# PQ60_EPS_FV3.net
KiCad netlist of a schematic drawn in EAGLE
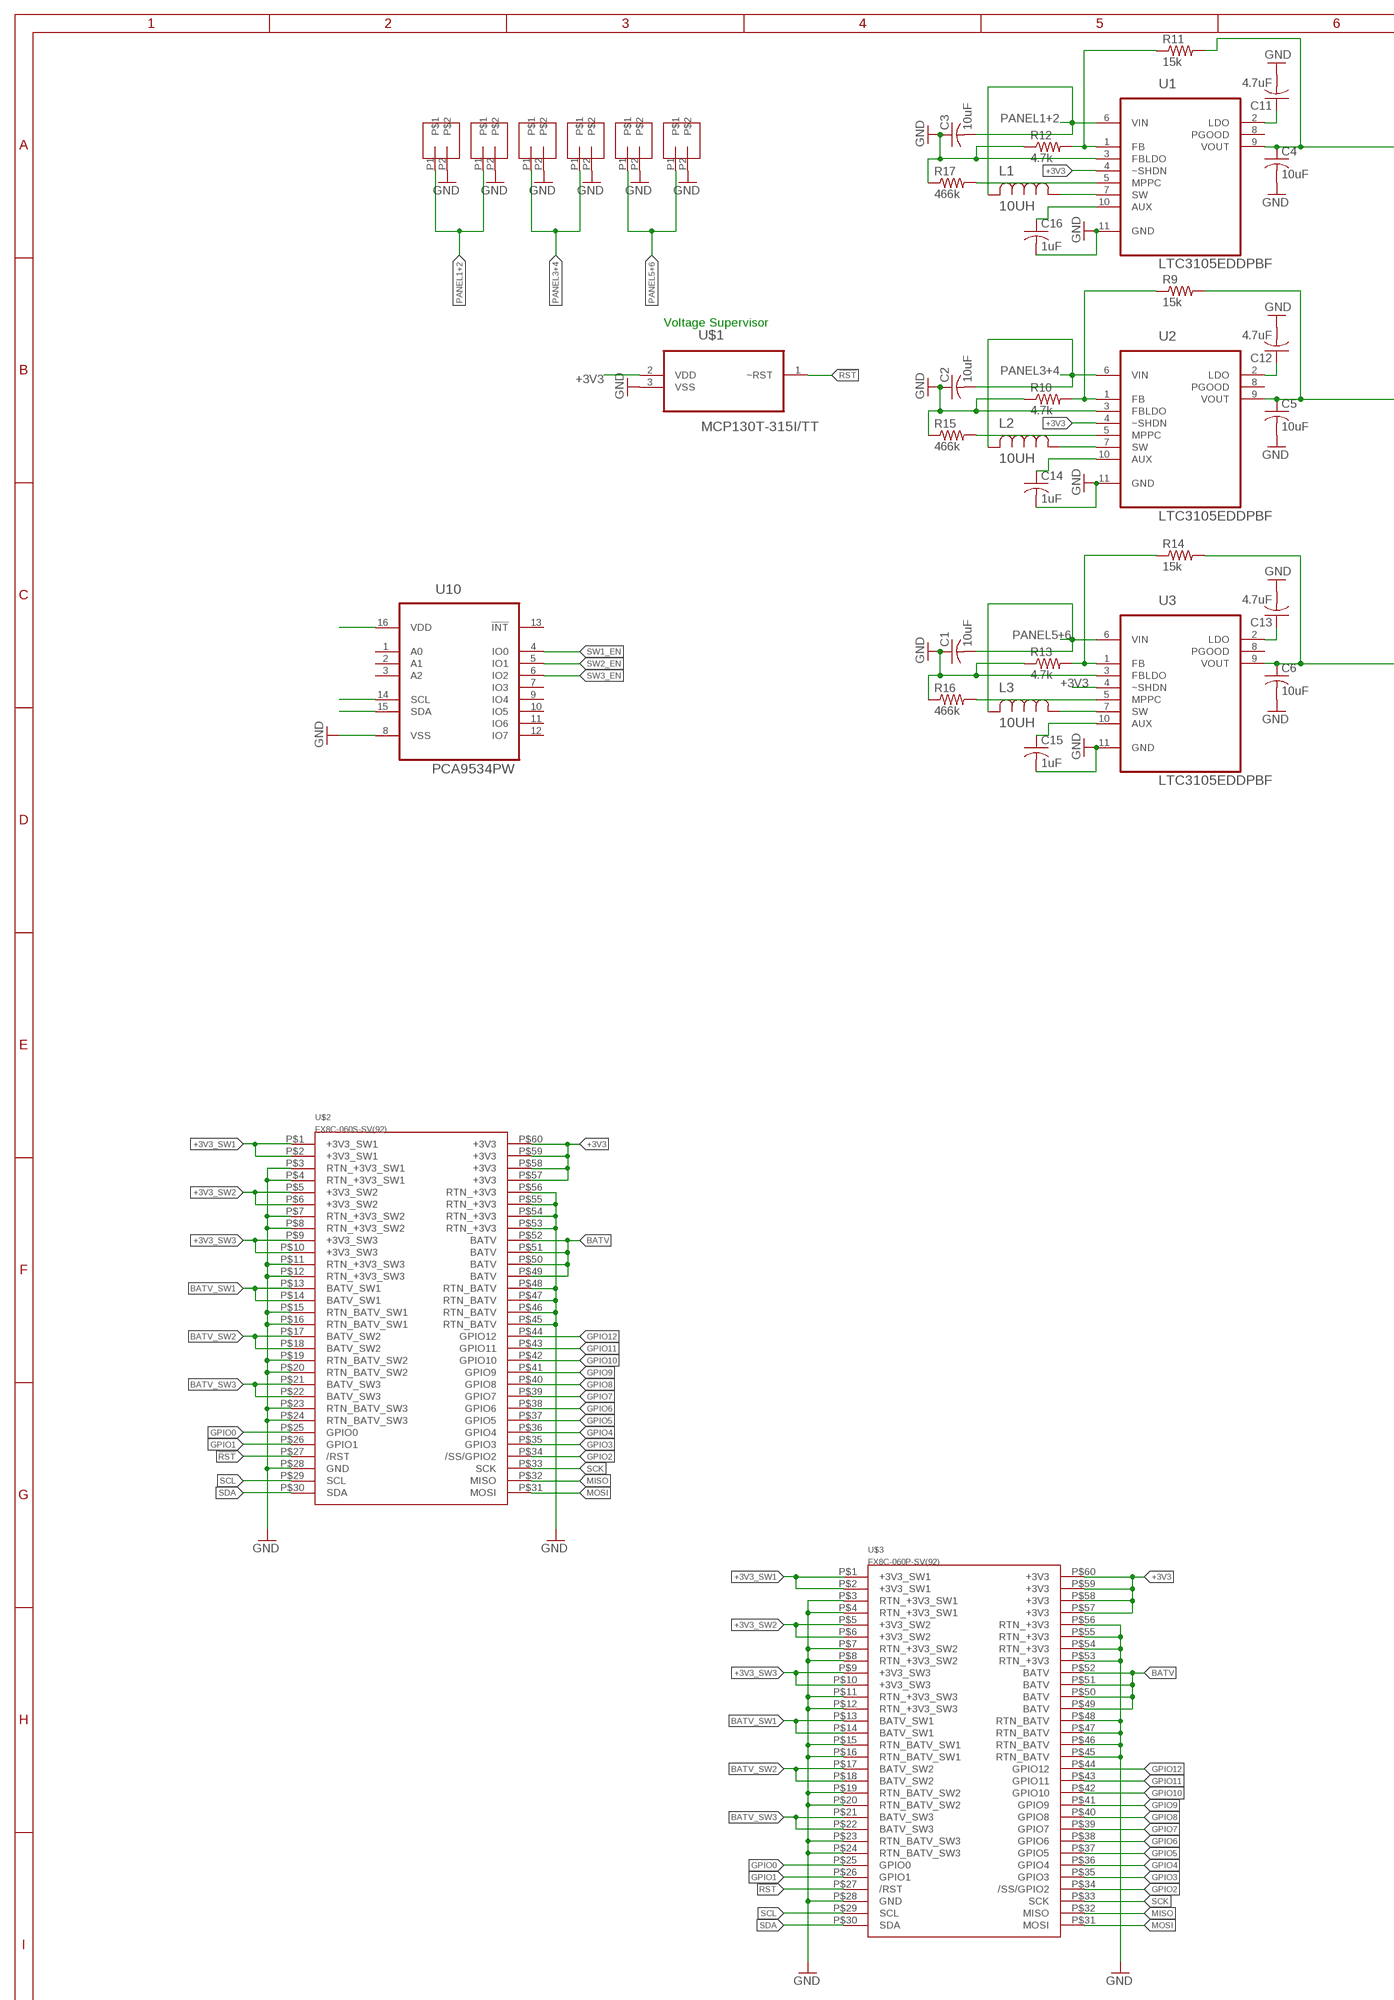
[diagram p0: schematic, sheet 1, part 1 of 2]
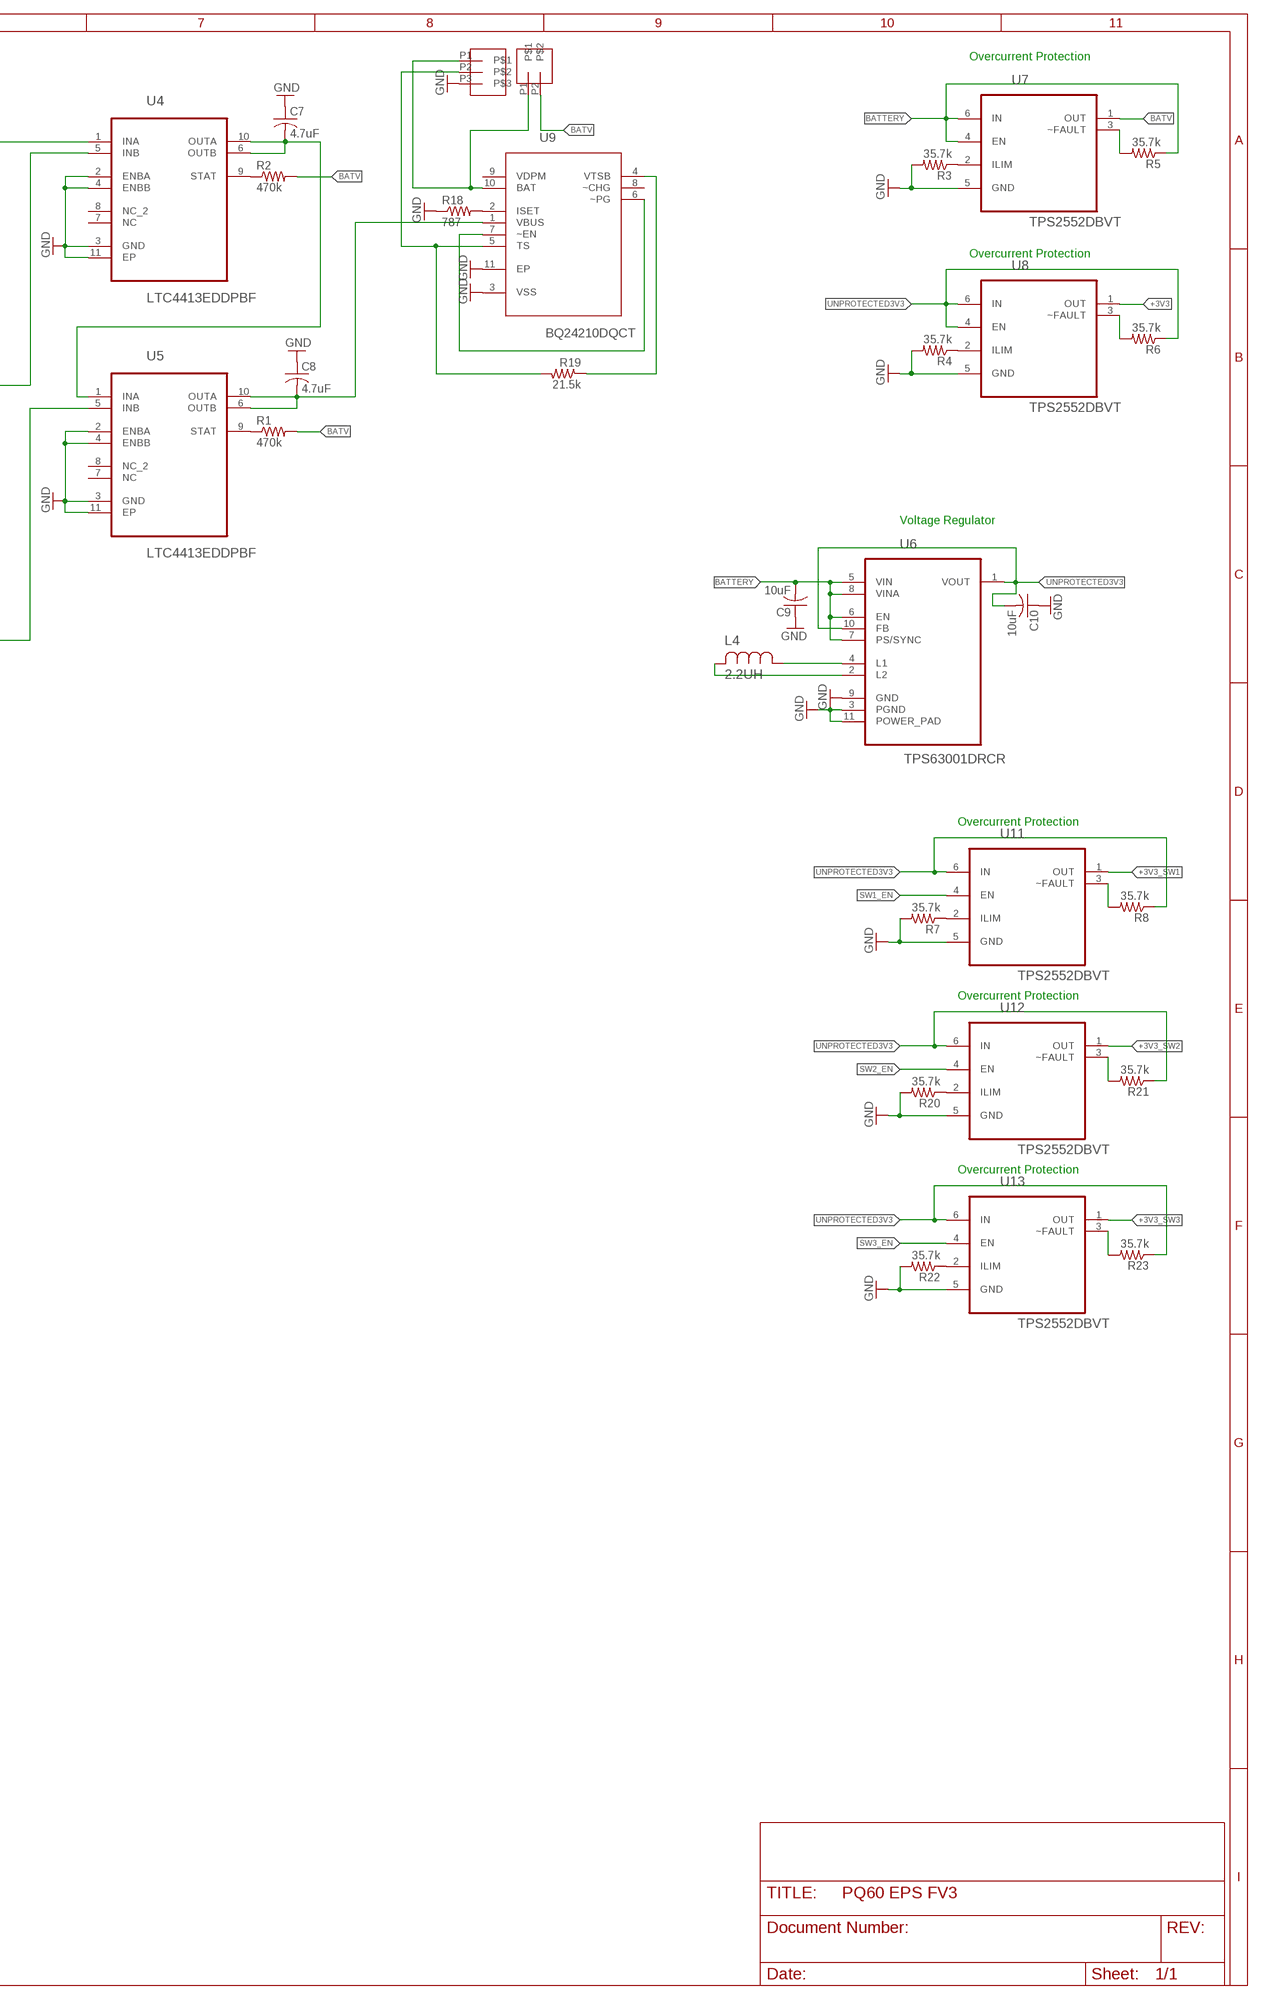
[diagram p1: schematic, sheet 1, part 2 of 2]

(export (version "E")
  (design (tool "Eeschema 10.0.6"))
  (components
    (comp (ref "C1")
      (value "10uF")
      (footprint "eagle-import:C0805")
      (libsource (lib "eagle-import") (part "C-USC0805"))
    )
    (comp (ref "C2")
      (value "10uF")
      (footprint "eagle-import:C0805")
      (libsource (lib "eagle-import") (part "C-USC0805"))
    )
    (comp (ref "C3")
      (value "10uF")
      (footprint "eagle-import:C0805")
      (libsource (lib "eagle-import") (part "C-USC0805"))
    )
    (comp (ref "C4")
      (value "10uF")
      (footprint "eagle-import:C0805")
      (libsource (lib "eagle-import") (part "C-USC0805"))
    )
    (comp (ref "C5")
      (value "10uF")
      (footprint "eagle-import:C0805")
      (libsource (lib "eagle-import") (part "C-USC0805"))
    )
    (comp (ref "C6")
      (value "10uF")
      (footprint "eagle-import:C0805")
      (libsource (lib "eagle-import") (part "C-USC0805"))
    )
    (comp (ref "C7")
      (value "4.7uF")
      (footprint "eagle-import:C0805")
      (libsource (lib "eagle-import") (part "C-USC0805"))
    )
    (comp (ref "C8")
      (value "4.7uF")
      (footprint "eagle-import:C0805")
      (libsource (lib "eagle-import") (part "C-USC0805"))
    )
    (comp (ref "C9")
      (value "10uF")
      (footprint "eagle-import:C0805")
      (libsource (lib "eagle-import") (part "C-USC0805"))
    )
    (comp (ref "C10")
      (value "10uF")
      (footprint "eagle-import:C0805")
      (libsource (lib "eagle-import") (part "C-USC0805"))
    )
    (comp (ref "C11")
      (value "4.7uF")
      (footprint "eagle-import:C0805")
      (libsource (lib "eagle-import") (part "C-USC0805"))
    )
    (comp (ref "C12")
      (value "4.7uF")
      (footprint "eagle-import:C0805")
      (libsource (lib "eagle-import") (part "C-USC0805"))
    )
    (comp (ref "C13")
      (value "4.7uF")
      (footprint "eagle-import:C0805")
      (libsource (lib "eagle-import") (part "C-USC0805"))
    )
    (comp (ref "C14")
      (value "1uF")
      (footprint "eagle-import:C0805")
      (libsource (lib "eagle-import") (part "C-USC0805"))
    )
    (comp (ref "C15")
      (value "1uF")
      (footprint "eagle-import:C0805")
      (libsource (lib "eagle-import") (part "C-USC0805"))
    )
    (comp (ref "C16")
      (value "1uF")
      (footprint "eagle-import:C0805")
      (libsource (lib "eagle-import") (part "C-USC0805"))
    )
    (comp (ref "L1")
      (value "10UH")
      (footprint "eagle-import:IND_ELL6XH")
      (fields (field (name "MPN") "ELL6SH100M"))
      (libsource (lib "eagle-import") (part "ELL-6XH6SH100M"))
    )
    (comp (ref "L2")
      (value "10UH")
      (footprint "eagle-import:IND_ELL6XH")
      (fields (field (name "MPN") "ELL6SH100M"))
      (libsource (lib "eagle-import") (part "ELL-6XH6SH100M"))
    )
    (comp (ref "L3")
      (value "10UH")
      (footprint "eagle-import:IND_ELL6XH")
      (fields (field (name "MPN") "ELL6SH100M"))
      (libsource (lib "eagle-import") (part "ELL-6XH6SH100M"))
    )
    (comp (ref "L4")
      (value "2.2UH")
      (footprint "eagle-import:IND_ELL3FU")
      (fields (field (name "MPN") "ELL3FU2R2N") (field (name "TOLERANCE") "±30 %"))
      (libsource (lib "eagle-import") (part "ELL-3FU3FU2R2N"))
    )
    (comp (ref "R1")
      (value "470k")
      (footprint "eagle-import:R0805")
      (libsource (lib "eagle-import") (part "R-US_R0805"))
    )
    (comp (ref "R2")
      (value "470k")
      (footprint "eagle-import:R0805")
      (libsource (lib "eagle-import") (part "R-US_R0805"))
    )
    (comp (ref "R3")
      (value "35.7k")
      (footprint "eagle-import:R0805")
      (libsource (lib "eagle-import") (part "R-US_R0805"))
    )
    (comp (ref "R4")
      (value "35.7k")
      (footprint "eagle-import:R0805")
      (libsource (lib "eagle-import") (part "R-US_R0805"))
    )
    (comp (ref "R5")
      (value "35.7k")
      (footprint "eagle-import:R0805")
      (libsource (lib "eagle-import") (part "R-US_R0805"))
    )
    (comp (ref "R6")
      (value "35.7k")
      (footprint "eagle-import:R0805")
      (libsource (lib "eagle-import") (part "R-US_R0805"))
    )
    (comp (ref "R7")
      (value "35.7k")
      (footprint "eagle-import:R0805")
      (libsource (lib "eagle-import") (part "R-US_R0805"))
    )
    (comp (ref "R8")
      (value "35.7k")
      (footprint "eagle-import:R0805")
      (libsource (lib "eagle-import") (part "R-US_R0805"))
    )
    (comp (ref "R9")
      (value "15k")
      (footprint "eagle-import:R0805")
      (libsource (lib "eagle-import") (part "R-US_R0805"))
    )
    (comp (ref "R10")
      (value "4.7k")
      (footprint "eagle-import:R0805")
      (libsource (lib "eagle-import") (part "R-US_R0805"))
    )
    (comp (ref "R11")
      (value "15k")
      (footprint "eagle-import:R0805")
      (libsource (lib "eagle-import") (part "R-US_R0805"))
    )
    (comp (ref "R12")
      (value "4.7k")
      (footprint "eagle-import:R0805")
      (libsource (lib "eagle-import") (part "R-US_R0805"))
    )
    (comp (ref "R13")
      (value "4.7k")
      (footprint "eagle-import:R0805")
      (libsource (lib "eagle-import") (part "R-US_R0805"))
    )
    (comp (ref "R14")
      (value "15k")
      (footprint "eagle-import:R0805")
      (libsource (lib "eagle-import") (part "R-US_R0805"))
    )
    (comp (ref "R15")
      (value "466k")
      (footprint "eagle-import:R0805")
      (libsource (lib "eagle-import") (part "R-US_R0805"))
    )
    (comp (ref "R16")
      (value "466k")
      (footprint "eagle-import:R0805")
      (libsource (lib "eagle-import") (part "R-US_R0805"))
    )
    (comp (ref "R17")
      (value "466k")
      (footprint "eagle-import:R0805")
      (libsource (lib "eagle-import") (part "R-US_R0805"))
    )
    (comp (ref "R18")
      (value "787")
      (footprint "eagle-import:R0805")
      (libsource (lib "eagle-import") (part "R-US_R0805"))
    )
    (comp (ref "R19")
      (value "21.5k")
      (footprint "eagle-import:R0805")
      (libsource (lib "eagle-import") (part "R-US_R0805"))
    )
    (comp (ref "R20")
      (value "35.7k")
      (footprint "eagle-import:R0805")
      (libsource (lib "eagle-import") (part "R-US_R0805"))
    )
    (comp (ref "R21")
      (value "35.7k")
      (footprint "eagle-import:R0805")
      (libsource (lib "eagle-import") (part "R-US_R0805"))
    )
    (comp (ref "R22")
      (value "35.7k")
      (footprint "eagle-import:R0805")
      (libsource (lib "eagle-import") (part "R-US_R0805"))
    )
    (comp (ref "R23")
      (value "35.7k")
      (footprint "eagle-import:R0805")
      (libsource (lib "eagle-import") (part "R-US_R0805"))
    )
    (comp (ref "U$1")
      (value "MCP130T-315I/TT")
      (footprint "eagle-import:SOT95P237X112-3N")
      (libsource (lib "eagle-import") (part "MCP130T-315I/TT"))
    )
    (comp (ref "U$2")
      (value "FX8C-060S-SV(92)")
      (footprint "eagle-import:FX8C-060S-SV(92)")
      (libsource (lib "eagle-import") (part "FX8C-060S-SV(92)"))
    )
    (comp (ref "U$3")
      (value "FX8C-060P-SV(92)")
      (footprint "eagle-import:FX8C-060P-SV(92)")
      (libsource (lib "eagle-import") (part "FX8C-060P-SV(92)"))
    )
    (comp (ref "U$4")
      (value "JST-SH-02")
      (footprint "eagle-import:JST-SH-02")
      (libsource (lib "eagle-import") (part "JST-SH-02"))
    )
    (comp (ref "U$5")
      (value "JST-SH-02")
      (footprint "eagle-import:JST-SH-02")
      (libsource (lib "eagle-import") (part "JST-SH-02"))
    )
    (comp (ref "U$6")
      (value "JST-SH-02")
      (footprint "eagle-import:JST-SH-02")
      (libsource (lib "eagle-import") (part "JST-SH-02"))
    )
    (comp (ref "U$7")
      (value "JST-SH-02")
      (footprint "eagle-import:JST-SH-02")
      (libsource (lib "eagle-import") (part "JST-SH-02"))
    )
    (comp (ref "U$8")
      (value "JST-SH-02")
      (footprint "eagle-import:JST-SH-02")
      (libsource (lib "eagle-import") (part "JST-SH-02"))
    )
    (comp (ref "U$9")
      (value "JST-SH-02")
      (footprint "eagle-import:JST-SH-02")
      (libsource (lib "eagle-import") (part "JST-SH-02"))
    )
    (comp (ref "U$10")
      (value "JST-SH-02")
      (footprint "eagle-import:JST-SH-02")
      (libsource (lib "eagle-import") (part "JST-SH-02"))
    )
    (comp (ref "U$11")
      (value "JST-SH-03")
      (footprint "eagle-import:JST-SH-03")
      (libsource (lib "eagle-import") (part "JST-SH-03"))
    )
    (comp (ref "U1")
      (value "LTC3105EDDPBF")
      (footprint "eagle-import:DFN300X300X80-11N")
      (fields (field (name "MPN") "LTC3105EDD#PBF"))
      (libsource (lib "eagle-import") (part "LTC3105EDDPBF"))
    )
    (comp (ref "U2")
      (value "LTC3105EDDPBF")
      (footprint "eagle-import:DFN300X300X80-11N")
      (fields (field (name "MPN") "LTC3105EDD#PBF"))
      (libsource (lib "eagle-import") (part "LTC3105EDDPBF"))
    )
    (comp (ref "U3")
      (value "LTC3105EDDPBF")
      (footprint "eagle-import:DFN300X300X80-11N")
      (fields (field (name "MPN") "LTC3105EDD#PBF"))
      (libsource (lib "eagle-import") (part "LTC3105EDDPBF"))
    )
    (comp (ref "U4")
      (value "LTC4413EDDPBF")
      (footprint "eagle-import:DFN300X300X80-11N")
      (fields (field (name "MPN") "LTC4413EDD#PBF"))
      (libsource (lib "eagle-import") (part "LTC4413EDDPBF"))
    )
    (comp (ref "U5")
      (value "LTC4413EDDPBF")
      (footprint "eagle-import:DFN300X300X80-11N")
      (fields (field (name "MPN") "LTC4413EDD#PBF"))
      (libsource (lib "eagle-import") (part "LTC4413EDDPBF"))
    )
    (comp (ref "U6")
      (value "TPS63001DRCR")
      (footprint "eagle-import:SON50P300X300X100-11N")
      (libsource (lib "eagle-import") (part "TPS63001DRCR"))
    )
    (comp (ref "U7")
      (value "TPS2552DBVT")
      (footprint "eagle-import:SOT95P280X145-6N")
      (libsource (lib "eagle-import") (part "TPS2552DBVT"))
    )
    (comp (ref "U8")
      (value "TPS2552DBVT")
      (footprint "eagle-import:SOT95P280X145-6N")
      (libsource (lib "eagle-import") (part "TPS2552DBVT"))
    )
    (comp (ref "U9")
      (value "BQ24210DQCT")
      (footprint "eagle-import:SON50P200X300X80-11N")
      (libsource (lib "eagle-import") (part "BQ24210DQCT"))
    )
    (comp (ref "U10")
      (value "PCA9534PW")
      (footprint "eagle-import:SOP65P640X110-16N")
      (libsource (lib "eagle-import") (part "PCA9534PW"))
    )
    (comp (ref "U11")
      (value "TPS2552DBVT")
      (footprint "eagle-import:SOT95P280X145-6N")
      (libsource (lib "eagle-import") (part "TPS2552DBVT"))
    )
    (comp (ref "U12")
      (value "TPS2552DBVT")
      (footprint "eagle-import:SOT95P280X145-6N")
      (libsource (lib "eagle-import") (part "TPS2552DBVT"))
    )
    (comp (ref "U13")
      (value "TPS2552DBVT")
      (footprint "eagle-import:SOT95P280X145-6N")
      (libsource (lib "eagle-import") (part "TPS2552DBVT"))
    )
  )
  (nets
    (net (code "1") (name "+3V3") (class "Default")
      (node (ref "U$1") (pin "2") (pinfunction "VDD_2") (pintype "power_in"))
      (node (ref "U$2") (pin "P$57") (pinfunction "+3V3_P$57") (pintype "power_in"))
      (node (ref "U$2") (pin "P$58") (pinfunction "+3V3_P$58") (pintype "power_in"))
      (node (ref "U$2") (pin "P$59") (pinfunction "+3V3_P$59") (pintype "power_in"))
      (node (ref "U$2") (pin "P$60") (pinfunction "+3V3_P$60") (pintype "power_in"))
      (node (ref "U$3") (pin "P$57") (pinfunction "+3V3_P$57") (pintype "power_in"))
      (node (ref "U$3") (pin "P$58") (pinfunction "+3V3_P$58") (pintype "power_in"))
      (node (ref "U$3") (pin "P$59") (pinfunction "+3V3_P$59") (pintype "power_in"))
      (node (ref "U$3") (pin "P$60") (pinfunction "+3V3_P$60") (pintype "power_in"))
      (node (ref "U1") (pin "4") (pinfunction "~{SHDN}_4") (pintype "input"))
      (node (ref "U10") (pin "16") (pinfunction "VDD_16") (pintype "power_in"))
      (node (ref "U2") (pin "4") (pinfunction "~{SHDN}_4") (pintype "input"))
      (node (ref "U3") (pin "4") (pinfunction "~{SHDN}_4") (pintype "input"))
      (node (ref "U8") (pin "1") (pinfunction "OUT_1") (pintype "output"))
    )
    (net (code "2") (name "+3V3_SW1") (class "Default")
      (node (ref "U$2") (pin "P$1") (pinfunction "+3V3_SW1_P$1") (pintype "power_in"))
      (node (ref "U$2") (pin "P$2") (pinfunction "+3V3_SW1_P$2") (pintype "power_in"))
      (node (ref "U$3") (pin "P$1") (pinfunction "+3V3_SW1_P$1") (pintype "power_in"))
      (node (ref "U$3") (pin "P$2") (pinfunction "+3V3_SW1_P$2") (pintype "power_in"))
      (node (ref "U11") (pin "1") (pinfunction "OUT_1") (pintype "output"))
    )
    (net (code "3") (name "+3V3_SW2") (class "Default")
      (node (ref "U$2") (pin "P$5") (pinfunction "+3V3_SW2_P$5") (pintype "power_in"))
      (node (ref "U$2") (pin "P$6") (pinfunction "+3V3_SW2_P$6") (pintype "power_in"))
      (node (ref "U$3") (pin "P$5") (pinfunction "+3V3_SW2_P$5") (pintype "power_in"))
      (node (ref "U$3") (pin "P$6") (pinfunction "+3V3_SW2_P$6") (pintype "power_in"))
      (node (ref "U12") (pin "1") (pinfunction "OUT_1") (pintype "output"))
    )
    (net (code "4") (name "+3V3_SW3") (class "Default")
      (node (ref "U$2") (pin "P$10") (pinfunction "+3V3_SW3_P$10") (pintype "power_in"))
      (node (ref "U$2") (pin "P$9") (pinfunction "+3V3_SW3_P$9") (pintype "power_in"))
      (node (ref "U$3") (pin "P$10") (pinfunction "+3V3_SW3_P$10") (pintype "power_in"))
      (node (ref "U$3") (pin "P$9") (pinfunction "+3V3_SW3_P$9") (pintype "power_in"))
      (node (ref "U13") (pin "1") (pinfunction "OUT_1") (pintype "output"))
    )
    (net (code "5") (name "/~{RST}") (class "Default")
      (node (ref "U$1") (pin "1") (pinfunction "~{RST}_1") (pintype "output"))
      (node (ref "U$2") (pin "P$27") (pinfunction "/RST_P$27") (pintype "bidirectional"))
      (node (ref "U$3") (pin "P$27") (pinfunction "/RST_P$27") (pintype "bidirectional"))
    )
    (net (code "6") (name "BATTERY") (class "Default")
      (node (ref "C9") (pin "2") (pinfunction "2_2") (pintype "passive"))
      (node (ref "R5") (pin "1") (pinfunction "1_1") (pintype "passive"))
      (node (ref "U6") (pin "5") (pinfunction "VIN_5") (pintype "power_in"))
      (node (ref "U6") (pin "6") (pinfunction "EN_6") (pintype "input"))
      (node (ref "U6") (pin "7") (pinfunction "PS/SYNC_7") (pintype "input"))
      (node (ref "U6") (pin "8") (pinfunction "VINA_8") (pintype "power_in"))
      (node (ref "U7") (pin "4") (pinfunction "EN_4") (pintype "input"))
      (node (ref "U7") (pin "6") (pinfunction "IN_6") (pintype "power_in"))
    )
    (net (code "7") (name "BATV") (class "Default")
      (node (ref "R1") (pin "2") (pinfunction "2_2") (pintype "passive"))
      (node (ref "R2") (pin "2") (pinfunction "2_2") (pintype "passive"))
      (node (ref "U$10") (pin "P2") (pinfunction "P$2_P2") (pintype "bidirectional"))
      (node (ref "U$2") (pin "P$49") (pinfunction "BATV_P$49") (pintype "power_in"))
      (node (ref "U$2") (pin "P$50") (pinfunction "BATV_P$50") (pintype "power_in"))
      (node (ref "U$2") (pin "P$51") (pinfunction "BATV_P$51") (pintype "power_in"))
      (node (ref "U$2") (pin "P$52") (pinfunction "BATV_P$52") (pintype "power_in"))
      (node (ref "U$3") (pin "P$49") (pinfunction "BATV_P$49") (pintype "power_in"))
      (node (ref "U$3") (pin "P$50") (pinfunction "BATV_P$50") (pintype "power_in"))
      (node (ref "U$3") (pin "P$51") (pinfunction "BATV_P$51") (pintype "power_in"))
      (node (ref "U$3") (pin "P$52") (pinfunction "BATV_P$52") (pintype "power_in"))
      (node (ref "U7") (pin "1") (pinfunction "OUT_1") (pintype "output"))
    )
    (net (code "8") (name "BATV_SW1") (class "Default")
      (node (ref "U$2") (pin "P$13") (pinfunction "BATV_SW1_P$13") (pintype "power_in"))
      (node (ref "U$2") (pin "P$14") (pinfunction "BATV_SW1_P$14") (pintype "power_in"))
      (node (ref "U$3") (pin "P$13") (pinfunction "BATV_SW1_P$13") (pintype "power_in"))
      (node (ref "U$3") (pin "P$14") (pinfunction "BATV_SW1_P$14") (pintype "power_in"))
    )
    (net (code "9") (name "BATV_SW2") (class "Default")
      (node (ref "U$2") (pin "P$17") (pinfunction "BATV_SW2_P$17") (pintype "power_in"))
      (node (ref "U$2") (pin "P$18") (pinfunction "BATV_SW2_P$18") (pintype "power_in"))
      (node (ref "U$3") (pin "P$17") (pinfunction "BATV_SW2_P$17") (pintype "power_in"))
      (node (ref "U$3") (pin "P$18") (pinfunction "BATV_SW2_P$18") (pintype "power_in"))
    )
    (net (code "10") (name "BATV_SW3") (class "Default")
      (node (ref "U$2") (pin "P$21") (pinfunction "BATV_SW3_P$21") (pintype "power_in"))
      (node (ref "U$2") (pin "P$22") (pinfunction "BATV_SW3_P$22") (pintype "power_in"))
      (node (ref "U$3") (pin "P$21") (pinfunction "BATV_SW3_P$21") (pintype "power_in"))
      (node (ref "U$3") (pin "P$22") (pinfunction "BATV_SW3_P$22") (pintype "power_in"))
    )
    (net (code "11") (name "GND") (class "Default")
      (node (ref "C1") (pin "1") (pinfunction "1_1") (pintype "passive"))
      (node (ref "C10") (pin "1") (pinfunction "1_1") (pintype "passive"))
      (node (ref "C11") (pin "2") (pinfunction "2_2") (pintype "passive"))
      (node (ref "C12") (pin "2") (pinfunction "2_2") (pintype "passive"))
      (node (ref "C13") (pin "2") (pinfunction "2_2") (pintype "passive"))
      (node (ref "C14") (pin "2") (pinfunction "2_2") (pintype "passive"))
      (node (ref "C15") (pin "2") (pinfunction "2_2") (pintype "passive"))
      (node (ref "C16") (pin "2") (pinfunction "2_2") (pintype "passive"))
      (node (ref "C2") (pin "1") (pinfunction "1_1") (pintype "passive"))
      (node (ref "C3") (pin "1") (pinfunction "1_1") (pintype "passive"))
      (node (ref "C4") (pin "2") (pinfunction "2_2") (pintype "passive"))
      (node (ref "C5") (pin "2") (pinfunction "2_2") (pintype "passive"))
      (node (ref "C6") (pin "2") (pinfunction "2_2") (pintype "passive"))
      (node (ref "C7") (pin "1") (pinfunction "1_1") (pintype "passive"))
      (node (ref "C8") (pin "1") (pinfunction "1_1") (pintype "passive"))
      (node (ref "C9") (pin "1") (pinfunction "1_1") (pintype "passive"))
      (node (ref "R10") (pin "1") (pinfunction "1_1") (pintype "passive"))
      (node (ref "R12") (pin "1") (pinfunction "1_1") (pintype "passive"))
      (node (ref "R13") (pin "1") (pinfunction "1_1") (pintype "passive"))
      (node (ref "R15") (pin "1") (pinfunction "1_1") (pintype "passive"))
      (node (ref "R16") (pin "1") (pinfunction "1_1") (pintype "passive"))
      (node (ref "R17") (pin "1") (pinfunction "1_1") (pintype "passive"))
      (node (ref "R18") (pin "1") (pinfunction "1_1") (pintype "passive"))
      (node (ref "R20") (pin "2") (pinfunction "2_2") (pintype "passive"))
      (node (ref "R22") (pin "2") (pinfunction "2_2") (pintype "passive"))
      (node (ref "R3") (pin "2") (pinfunction "2_2") (pintype "passive"))
      (node (ref "R4") (pin "2") (pinfunction "2_2") (pintype "passive"))
      (node (ref "R7") (pin "2") (pinfunction "2_2") (pintype "passive"))
      (node (ref "U$1") (pin "3") (pinfunction "VSS_3") (pintype "power_in"))
      (node (ref "U$11") (pin "P3") (pinfunction "P$3_P3") (pintype "bidirectional"))
      (node (ref "U$2") (pin "P$11") (pinfunction "RTN_+3V3_SW3_P$11") (pintype "power_in"))
      (node (ref "U$2") (pin "P$12") (pinfunction "RTN_+3V3_SW3_P$12") (pintype "power_in"))
      (node (ref "U$2") (pin "P$15") (pinfunction "RTN_BATV_SW1_P$15") (pintype "power_in"))
      (node (ref "U$2") (pin "P$16") (pinfunction "RTN_BATV_SW1_P$16") (pintype "power_in"))
      (node (ref "U$2") (pin "P$19") (pinfunction "RTN_BATV_SW2_P$19") (pintype "power_in"))
      (node (ref "U$2") (pin "P$20") (pinfunction "RTN_BATV_SW2_P$20") (pintype "power_in"))
      (node (ref "U$2") (pin "P$23") (pinfunction "RTN_BATV_SW3_P$23") (pintype "power_in"))
      (node (ref "U$2") (pin "P$24") (pinfunction "RTN_BATV_SW3_P$24") (pintype "power_in"))
      (node (ref "U$2") (pin "P$28") (pinfunction "GND_P$28") (pintype "bidirectional"))
      (node (ref "U$2") (pin "P$3") (pinfunction "RTN_+3V3_SW1_P$3") (pintype "power_in"))
      (node (ref "U$2") (pin "P$4") (pinfunction "RTN_+3V3_SW1_P$4") (pintype "power_in"))
      (node (ref "U$2") (pin "P$45") (pinfunction "RTN_BATV_P$45") (pintype "power_in"))
      (node (ref "U$2") (pin "P$46") (pinfunction "RTN_BATV_P$46") (pintype "power_in"))
      (node (ref "U$2") (pin "P$47") (pinfunction "RTN_BATV_P$47") (pintype "power_in"))
      (node (ref "U$2") (pin "P$48") (pinfunction "RTN_BATV_P$48") (pintype "power_in"))
      (node (ref "U$2") (pin "P$53") (pinfunction "RTN_+3V3_P$53") (pintype "power_in"))
      (node (ref "U$2") (pin "P$54") (pinfunction "RTN_+3V3_P$54") (pintype "power_in"))
      (node (ref "U$2") (pin "P$55") (pinfunction "RTN_+3V3_P$55") (pintype "power_in"))
      (node (ref "U$2") (pin "P$56") (pinfunction "RTN_+3V3_P$56") (pintype "power_in"))
      (node (ref "U$2") (pin "P$7") (pinfunction "RTN_+3V3_SW2_P$7") (pintype "power_in"))
      (node (ref "U$2") (pin "P$8") (pinfunction "RTN_+3V3_SW2_P$8") (pintype "power_in"))
      (node (ref "U$3") (pin "P$11") (pinfunction "RTN_+3V3_SW3_P$11") (pintype "power_in"))
      (node (ref "U$3") (pin "P$12") (pinfunction "RTN_+3V3_SW3_P$12") (pintype "power_in"))
      (node (ref "U$3") (pin "P$15") (pinfunction "RTN_BATV_SW1_P$15") (pintype "power_in"))
      (node (ref "U$3") (pin "P$16") (pinfunction "RTN_BATV_SW1_P$16") (pintype "power_in"))
      (node (ref "U$3") (pin "P$19") (pinfunction "RTN_BATV_SW2_P$19") (pintype "power_in"))
      (node (ref "U$3") (pin "P$20") (pinfunction "RTN_BATV_SW2_P$20") (pintype "power_in"))
      (node (ref "U$3") (pin "P$23") (pinfunction "RTN_BATV_SW3_P$23") (pintype "power_in"))
      (node (ref "U$3") (pin "P$24") (pinfunction "RTN_BATV_SW3_P$24") (pintype "power_in"))
      (node (ref "U$3") (pin "P$28") (pinfunction "GND_P$28") (pintype "bidirectional"))
      (node (ref "U$3") (pin "P$3") (pinfunction "RTN_+3V3_SW1_P$3") (pintype "power_in"))
      (node (ref "U$3") (pin "P$4") (pinfunction "RTN_+3V3_SW1_P$4") (pintype "power_in"))
      (node (ref "U$3") (pin "P$45") (pinfunction "RTN_BATV_P$45") (pintype "power_in"))
      (node (ref "U$3") (pin "P$46") (pinfunction "RTN_BATV_P$46") (pintype "power_in"))
      (node (ref "U$3") (pin "P$47") (pinfunction "RTN_BATV_P$47") (pintype "power_in"))
      (node (ref "U$3") (pin "P$48") (pinfunction "RTN_BATV_P$48") (pintype "power_in"))
      (node (ref "U$3") (pin "P$53") (pinfunction "RTN_+3V3_P$53") (pintype "power_in"))
      (node (ref "U$3") (pin "P$54") (pinfunction "RTN_+3V3_P$54") (pintype "power_in"))
      (node (ref "U$3") (pin "P$55") (pinfunction "RTN_+3V3_P$55") (pintype "power_in"))
      (node (ref "U$3") (pin "P$56") (pinfunction "RTN_+3V3_P$56") (pintype "power_in"))
      (node (ref "U$3") (pin "P$7") (pinfunction "RTN_+3V3_SW2_P$7") (pintype "power_in"))
      (node (ref "U$3") (pin "P$8") (pinfunction "RTN_+3V3_SW2_P$8") (pintype "power_in"))
      (node (ref "U$4") (pin "P2") (pinfunction "P$2_P2") (pintype "bidirectional"))
      (node (ref "U$5") (pin "P2") (pinfunction "P$2_P2") (pintype "bidirectional"))
      (node (ref "U$6") (pin "P2") (pinfunction "P$2_P2") (pintype "bidirectional"))
      (node (ref "U$7") (pin "P2") (pinfunction "P$2_P2") (pintype "bidirectional"))
      (node (ref "U$8") (pin "P2") (pinfunction "P$2_P2") (pintype "bidirectional"))
      (node (ref "U$9") (pin "P2") (pinfunction "P$2_P2") (pintype "bidirectional"))
      (node (ref "U1") (pin "11") (pinfunction "GND_11") (pintype "passive"))
      (node (ref "U1") (pin "3") (pinfunction "FBLDO_3") (pintype "input"))
      (node (ref "U10") (pin "8") (pinfunction "VSS_8") (pintype "passive"))
      (node (ref "U11") (pin "5") (pinfunction "GND_5") (pintype "passive"))
      (node (ref "U12") (pin "5") (pinfunction "GND_5") (pintype "passive"))
      (node (ref "U13") (pin "5") (pinfunction "GND_5") (pintype "passive"))
      (node (ref "U2") (pin "11") (pinfunction "GND_11") (pintype "passive"))
      (node (ref "U2") (pin "3") (pinfunction "FBLDO_3") (pintype "input"))
      (node (ref "U3") (pin "11") (pinfunction "GND_11") (pintype "passive"))
      (node (ref "U3") (pin "3") (pinfunction "FBLDO_3") (pintype "input"))
      (node (ref "U4") (pin "11") (pinfunction "EP_11") (pintype "passive"))
      (node (ref "U4") (pin "2") (pinfunction "ENBA_2") (pintype "input"))
      (node (ref "U4") (pin "3") (pinfunction "GND_3") (pintype "passive"))
      (node (ref "U4") (pin "4") (pinfunction "ENBB_4") (pintype "input"))
      (node (ref "U5") (pin "11") (pinfunction "EP_11") (pintype "passive"))
      (node (ref "U5") (pin "2") (pinfunction "ENBA_2") (pintype "input"))
      (node (ref "U5") (pin "3") (pinfunction "GND_3") (pintype "passive"))
      (node (ref "U5") (pin "4") (pinfunction "ENBB_4") (pintype "input"))
      (node (ref "U6") (pin "11") (pinfunction "POWER_PAD_11") (pintype "passive"))
      (node (ref "U6") (pin "3") (pinfunction "PGND_3") (pintype "passive"))
      (node (ref "U6") (pin "9") (pinfunction "GND_9") (pintype "passive"))
      (node (ref "U7") (pin "5") (pinfunction "GND_5") (pintype "passive"))
      (node (ref "U8") (pin "5") (pinfunction "GND_5") (pintype "passive"))
      (node (ref "U9") (pin "11") (pinfunction "EP_11") (pintype "passive"))
      (node (ref "U9") (pin "3") (pinfunction "VSS_3") (pintype "passive"))
    )
    (net (code "12") (name "GPIO0") (class "Default")
      (node (ref "U$2") (pin "P$25") (pinfunction "GPIO0_P$25") (pintype "bidirectional"))
      (node (ref "U$3") (pin "P$25") (pinfunction "GPIO0_P$25") (pintype "bidirectional"))
    )
    (net (code "13") (name "GPIO1") (class "Default")
      (node (ref "U$2") (pin "P$26") (pinfunction "GPIO1_P$26") (pintype "bidirectional"))
      (node (ref "U$3") (pin "P$26") (pinfunction "GPIO1_P$26") (pintype "bidirectional"))
    )
    (net (code "14") (name "GPIO2") (class "Default")
      (node (ref "U$2") (pin "P$34") (pinfunction "/SS/GPIO2_P$34") (pintype "bidirectional"))
      (node (ref "U$3") (pin "P$34") (pinfunction "/SS/GPIO2_P$34") (pintype "bidirectional"))
    )
    (net (code "15") (name "GPIO3") (class "Default")
      (node (ref "U$2") (pin "P$35") (pinfunction "GPIO3_P$35") (pintype "bidirectional"))
      (node (ref "U$3") (pin "P$35") (pinfunction "GPIO3_P$35") (pintype "bidirectional"))
    )
    (net (code "16") (name "GPIO4") (class "Default")
      (node (ref "U$2") (pin "P$36") (pinfunction "GPIO4_P$36") (pintype "bidirectional"))
      (node (ref "U$3") (pin "P$36") (pinfunction "GPIO4_P$36") (pintype "bidirectional"))
    )
    (net (code "17") (name "GPIO5") (class "Default")
      (node (ref "U$2") (pin "P$37") (pinfunction "GPIO5_P$37") (pintype "bidirectional"))
      (node (ref "U$3") (pin "P$37") (pinfunction "GPIO5_P$37") (pintype "bidirectional"))
    )
    (net (code "18") (name "GPIO6") (class "Default")
      (node (ref "U$2") (pin "P$38") (pinfunction "GPIO6_P$38") (pintype "bidirectional"))
      (node (ref "U$3") (pin "P$38") (pinfunction "GPIO6_P$38") (pintype "bidirectional"))
    )
    (net (code "19") (name "GPIO7") (class "Default")
      (node (ref "U$2") (pin "P$39") (pinfunction "GPIO7_P$39") (pintype "bidirectional"))
      (node (ref "U$3") (pin "P$39") (pinfunction "GPIO7_P$39") (pintype "bidirectional"))
    )
    (net (code "20") (name "GPIO8") (class "Default")
      (node (ref "U$2") (pin "P$40") (pinfunction "GPIO8_P$40") (pintype "bidirectional"))
      (node (ref "U$3") (pin "P$40") (pinfunction "GPIO8_P$40") (pintype "bidirectional"))
    )
    (net (code "21") (name "GPIO9") (class "Default")
      (node (ref "U$2") (pin "P$41") (pinfunction "GPIO9_P$41") (pintype "bidirectional"))
      (node (ref "U$3") (pin "P$41") (pinfunction "GPIO9_P$41") (pintype "bidirectional"))
    )
    (net (code "22") (name "GPIO10") (class "Default")
      (node (ref "U$2") (pin "P$42") (pinfunction "GPIO10_P$42") (pintype "bidirectional"))
      (node (ref "U$3") (pin "P$42") (pinfunction "GPIO10_P$42") (pintype "bidirectional"))
    )
    (net (code "23") (name "GPIO11") (class "Default")
      (node (ref "U$2") (pin "P$43") (pinfunction "GPIO11_P$43") (pintype "bidirectional"))
      (node (ref "U$3") (pin "P$43") (pinfunction "GPIO11_P$43") (pintype "bidirectional"))
    )
    (net (code "24") (name "GPIO12") (class "Default")
      (node (ref "U$2") (pin "P$44") (pinfunction "GPIO12_P$44") (pintype "bidirectional"))
      (node (ref "U$3") (pin "P$44") (pinfunction "GPIO12_P$44") (pintype "bidirectional"))
    )
    (net (code "25") (name "MISO") (class "Default")
      (node (ref "U$2") (pin "P$32") (pinfunction "MISO_P$32") (pintype "bidirectional"))
      (node (ref "U$3") (pin "P$32") (pinfunction "MISO_P$32") (pintype "bidirectional"))
    )
    (net (code "26") (name "MOSI") (class "Default")
      (node (ref "U$2") (pin "P$31") (pinfunction "MOSI_P$31") (pintype "bidirectional"))
      (node (ref "U$3") (pin "P$31") (pinfunction "MOSI_P$31") (pintype "bidirectional"))
    )
    (net (code "27") (name "Net-(U$10-P$1)") (class "Default")
      (node (ref "U$10") (pin "P1") (pinfunction "P$1_P1") (pintype "bidirectional"))
      (node (ref "U$11") (pin "P1") (pinfunction "P$1_P1") (pintype "bidirectional"))
      (node (ref "U9") (pin "10") (pinfunction "BAT_10") (pintype "bidirectional"))
    )
    (net (code "28") (name "Net-(U$11-P$2)") (class "Default")
      (node (ref "R19") (pin "2") (pinfunction "2_2") (pintype "passive"))
      (node (ref "U$11") (pin "P2") (pinfunction "P$2_P2") (pintype "bidirectional"))
      (node (ref "U9") (pin "5") (pinfunction "TS_5") (pintype "input"))
    )
    (net (code "29") (name "Net-(U1-AUX)") (class "Default")
      (node (ref "C16") (pin "1") (pinfunction "1_1") (pintype "passive"))
      (node (ref "U1") (pin "10") (pinfunction "AUX_10") (pintype "passive"))
    )
    (net (code "30") (name "Net-(U1-FB)") (class "Default")
      (node (ref "R11") (pin "1") (pinfunction "1_1") (pintype "passive"))
      (node (ref "R12") (pin "2") (pinfunction "2_2") (pintype "passive"))
      (node (ref "U1") (pin "1") (pinfunction "FB_1") (pintype "input"))
    )
    (net (code "31") (name "Net-(U1-LDO)") (class "Default")
      (node (ref "C11") (pin "1") (pinfunction "1_1") (pintype "passive"))
      (node (ref "U1") (pin "2") (pinfunction "LDO_2") (pintype "output"))
    )
    (net (code "32") (name "Net-(U1-MPPC)") (class "Default")
      (node (ref "R17") (pin "2") (pinfunction "2_2") (pintype "passive"))
      (node (ref "U1") (pin "5") (pinfunction "MPPC_5") (pintype "input"))
    )
    (net (code "33") (name "Net-(U1-SW)") (class "Default")
      (node (ref "L1") (pin "1") (pinfunction "1_1") (pintype "passive"))
      (node (ref "U1") (pin "7") (pinfunction "SW_7") (pintype "passive"))
    )
    (net (code "34") (name "Net-(U1-VOUT)") (class "Default")
      (node (ref "C4") (pin "1") (pinfunction "1_1") (pintype "passive"))
      (node (ref "R11") (pin "2") (pinfunction "2_2") (pintype "passive"))
      (node (ref "U1") (pin "9") (pinfunction "VOUT_9") (pintype "output"))
      (node (ref "U4") (pin "1") (pinfunction "INA_1") (pintype "power_in"))
    )
    (net (code "35") (name "Net-(U2-AUX)") (class "Default")
      (node (ref "C14") (pin "1") (pinfunction "1_1") (pintype "passive"))
      (node (ref "U2") (pin "10") (pinfunction "AUX_10") (pintype "passive"))
    )
    (net (code "36") (name "Net-(U2-FB)") (class "Default")
      (node (ref "R10") (pin "2") (pinfunction "2_2") (pintype "passive"))
      (node (ref "R9") (pin "1") (pinfunction "1_1") (pintype "passive"))
      (node (ref "U2") (pin "1") (pinfunction "FB_1") (pintype "input"))
    )
    (net (code "37") (name "Net-(U2-LDO)") (class "Default")
      (node (ref "C12") (pin "1") (pinfunction "1_1") (pintype "passive"))
      (node (ref "U2") (pin "2") (pinfunction "LDO_2") (pintype "output"))
    )
    (net (code "38") (name "Net-(U2-MPPC)") (class "Default")
      (node (ref "R15") (pin "2") (pinfunction "2_2") (pintype "passive"))
      (node (ref "U2") (pin "5") (pinfunction "MPPC_5") (pintype "input"))
    )
    (net (code "39") (name "Net-(U2-SW)") (class "Default")
      (node (ref "L2") (pin "1") (pinfunction "1_1") (pintype "passive"))
      (node (ref "U2") (pin "7") (pinfunction "SW_7") (pintype "passive"))
    )
    (net (code "40") (name "Net-(U2-VOUT)") (class "Default")
      (node (ref "C5") (pin "1") (pinfunction "1_1") (pintype "passive"))
      (node (ref "R9") (pin "2") (pinfunction "2_2") (pintype "passive"))
      (node (ref "U2") (pin "9") (pinfunction "VOUT_9") (pintype "output"))
      (node (ref "U4") (pin "5") (pinfunction "INB_5") (pintype "power_in"))
    )
    (net (code "41") (name "Net-(U3-AUX)") (class "Default")
      (node (ref "C15") (pin "1") (pinfunction "1_1") (pintype "passive"))
      (node (ref "U3") (pin "10") (pinfunction "AUX_10") (pintype "passive"))
    )
    (net (code "42") (name "Net-(U3-FB)") (class "Default")
      (node (ref "R13") (pin "2") (pinfunction "2_2") (pintype "passive"))
      (node (ref "R14") (pin "1") (pinfunction "1_1") (pintype "passive"))
      (node (ref "U3") (pin "1") (pinfunction "FB_1") (pintype "input"))
    )
    (net (code "43") (name "Net-(U3-LDO)") (class "Default")
      (node (ref "C13") (pin "1") (pinfunction "1_1") (pintype "passive"))
      (node (ref "U3") (pin "2") (pinfunction "LDO_2") (pintype "output"))
    )
    (net (code "44") (name "Net-(U3-MPPC)") (class "Default")
      (node (ref "R16") (pin "2") (pinfunction "2_2") (pintype "passive"))
      (node (ref "U3") (pin "5") (pinfunction "MPPC_5") (pintype "input"))
    )
    (net (code "45") (name "Net-(U3-SW)") (class "Default")
      (node (ref "L3") (pin "1") (pinfunction "1_1") (pintype "passive"))
      (node (ref "U3") (pin "7") (pinfunction "SW_7") (pintype "passive"))
    )
    (net (code "46") (name "Net-(U3-VOUT)") (class "Default")
      (node (ref "C6") (pin "1") (pinfunction "1_1") (pintype "passive"))
      (node (ref "R14") (pin "2") (pinfunction "2_2") (pintype "passive"))
      (node (ref "U3") (pin "9") (pinfunction "VOUT_9") (pintype "output"))
      (node (ref "U5") (pin "5") (pinfunction "INB_5") (pintype "power_in"))
    )
    (net (code "47") (name "Net-(U4-OUTA)") (class "Default")
      (node (ref "C7") (pin "2") (pinfunction "2_2") (pintype "passive"))
      (node (ref "U4") (pin "10") (pinfunction "OUTA_10") (pintype "output"))
      (node (ref "U4") (pin "6") (pinfunction "OUTB_6") (pintype "output"))
      (node (ref "U5") (pin "1") (pinfunction "INA_1") (pintype "power_in"))
    )
    (net (code "48") (name "Net-(U4-STAT)") (class "Default")
      (node (ref "R2") (pin "1") (pinfunction "1_1") (pintype "passive"))
      (node (ref "U4") (pin "9") (pinfunction "STAT_9") (pintype "output"))
    )
    (net (code "49") (name "Net-(U5-OUTA)") (class "Default")
      (node (ref "C8") (pin "2") (pinfunction "2_2") (pintype "passive"))
      (node (ref "U5") (pin "10") (pinfunction "OUTA_10") (pintype "output"))
      (node (ref "U5") (pin "6") (pinfunction "OUTB_6") (pintype "output"))
      (node (ref "U9") (pin "1") (pinfunction "VBUS_1") (pintype "bidirectional"))
    )
    (net (code "50") (name "Net-(U5-STAT)") (class "Default")
      (node (ref "R1") (pin "1") (pinfunction "1_1") (pintype "passive"))
      (node (ref "U5") (pin "9") (pinfunction "STAT_9") (pintype "output"))
    )
    (net (code "51") (name "Net-(U6-L1)") (class "Default")
      (node (ref "L4") (pin "1") (pinfunction "1_1") (pintype "passive"))
      (node (ref "U6") (pin "4") (pinfunction "L1_4") (pintype "passive"))
    )
    (net (code "52") (name "Net-(U6-L2)") (class "Default")
      (node (ref "L4") (pin "2") (pinfunction "2_2") (pintype "passive"))
      (node (ref "U6") (pin "2") (pinfunction "L2_2") (pintype "passive"))
    )
    (net (code "53") (name "Net-(U7-ILIM)") (class "Default")
      (node (ref "R3") (pin "1") (pinfunction "1_1") (pintype "passive"))
      (node (ref "U7") (pin "2") (pinfunction "ILIM_2") (pintype "input"))
    )
    (net (code "54") (name "Net-(U7-~{FAULT})") (class "Default")
      (node (ref "R5") (pin "2") (pinfunction "2_2") (pintype "passive"))
      (node (ref "U7") (pin "3") (pinfunction "~{FAULT}_3") (pintype "output"))
    )
    (net (code "55") (name "Net-(U8-ILIM)") (class "Default")
      (node (ref "R4") (pin "1") (pinfunction "1_1") (pintype "passive"))
      (node (ref "U8") (pin "2") (pinfunction "ILIM_2") (pintype "input"))
    )
    (net (code "56") (name "Net-(U8-~{FAULT})") (class "Default")
      (node (ref "R6") (pin "2") (pinfunction "2_2") (pintype "passive"))
      (node (ref "U8") (pin "3") (pinfunction "~{FAULT}_3") (pintype "output"))
    )
    (net (code "57") (name "Net-(U9-ISET)") (class "Default")
      (node (ref "R18") (pin "2") (pinfunction "2_2") (pintype "passive"))
      (node (ref "U9") (pin "2") (pinfunction "ISET_2") (pintype "input"))
    )
    (net (code "58") (name "Net-(U9-VTSB)") (class "Default")
      (node (ref "R19") (pin "1") (pinfunction "1_1") (pintype "passive"))
      (node (ref "U9") (pin "4") (pinfunction "VTSB_4") (pintype "output"))
    )
    (net (code "59") (name "Net-(U9-~{EN})") (class "Default")
      (node (ref "U9") (pin "6") (pinfunction "~{PG}_6") (pintype "output"))
      (node (ref "U9") (pin "7") (pinfunction "~{EN}_7") (pintype "input"))
    )
    (net (code "60") (name "Net-(U11-ILIM)") (class "Default")
      (node (ref "R7") (pin "1") (pinfunction "1_1") (pintype "passive"))
      (node (ref "U11") (pin "2") (pinfunction "ILIM_2") (pintype "input"))
    )
    (net (code "61") (name "Net-(U11-~{FAULT})") (class "Default")
      (node (ref "R8") (pin "2") (pinfunction "2_2") (pintype "passive"))
      (node (ref "U11") (pin "3") (pinfunction "~{FAULT}_3") (pintype "output"))
    )
    (net (code "62") (name "Net-(U12-ILIM)") (class "Default")
      (node (ref "R20") (pin "1") (pinfunction "1_1") (pintype "passive"))
      (node (ref "U12") (pin "2") (pinfunction "ILIM_2") (pintype "input"))
    )
    (net (code "63") (name "Net-(U12-~{FAULT})") (class "Default")
      (node (ref "R21") (pin "2") (pinfunction "2_2") (pintype "passive"))
      (node (ref "U12") (pin "3") (pinfunction "~{FAULT}_3") (pintype "output"))
    )
    (net (code "64") (name "Net-(U13-ILIM)") (class "Default")
      (node (ref "R22") (pin "1") (pinfunction "1_1") (pintype "passive"))
      (node (ref "U13") (pin "2") (pinfunction "ILIM_2") (pintype "input"))
    )
    (net (code "65") (name "Net-(U13-~{FAULT})") (class "Default")
      (node (ref "R23") (pin "2") (pinfunction "2_2") (pintype "passive"))
      (node (ref "U13") (pin "3") (pinfunction "~{FAULT}_3") (pintype "output"))
    )
    (net (code "66") (name "PANEL1+2") (class "Default")
      (node (ref "C3") (pin "2") (pinfunction "2_2") (pintype "passive"))
      (node (ref "L1") (pin "2") (pinfunction "2_2") (pintype "passive"))
      (node (ref "U$4") (pin "P1") (pinfunction "P$1_P1") (pintype "bidirectional"))
      (node (ref "U$5") (pin "P1") (pinfunction "P$1_P1") (pintype "bidirectional"))
      (node (ref "U1") (pin "6") (pinfunction "VIN_6") (pintype "power_in"))
    )
    (net (code "67") (name "PANEL3+4") (class "Default")
      (node (ref "C2") (pin "2") (pinfunction "2_2") (pintype "passive"))
      (node (ref "L2") (pin "2") (pinfunction "2_2") (pintype "passive"))
      (node (ref "U$6") (pin "P1") (pinfunction "P$1_P1") (pintype "bidirectional"))
      (node (ref "U$7") (pin "P1") (pinfunction "P$1_P1") (pintype "bidirectional"))
      (node (ref "U2") (pin "6") (pinfunction "VIN_6") (pintype "power_in"))
    )
    (net (code "68") (name "PANEL5+6") (class "Default")
      (node (ref "C1") (pin "2") (pinfunction "2_2") (pintype "passive"))
      (node (ref "L3") (pin "2") (pinfunction "2_2") (pintype "passive"))
      (node (ref "U$8") (pin "P1") (pinfunction "P$1_P1") (pintype "bidirectional"))
      (node (ref "U$9") (pin "P1") (pinfunction "P$1_P1") (pintype "bidirectional"))
      (node (ref "U3") (pin "6") (pinfunction "VIN_6") (pintype "power_in"))
    )
    (net (code "69") (name "SCK") (class "Default")
      (node (ref "U$2") (pin "P$33") (pinfunction "SCK_P$33") (pintype "bidirectional"))
      (node (ref "U$3") (pin "P$33") (pinfunction "SCK_P$33") (pintype "bidirectional"))
    )
    (net (code "70") (name "SCL") (class "Default")
      (node (ref "U$2") (pin "P$29") (pinfunction "SCL_P$29") (pintype "bidirectional"))
      (node (ref "U$3") (pin "P$29") (pinfunction "SCL_P$29") (pintype "bidirectional"))
      (node (ref "U10") (pin "14") (pinfunction "SCL_14") (pintype "bidirectional"))
    )
    (net (code "71") (name "SDA") (class "Default")
      (node (ref "U$2") (pin "P$30") (pinfunction "SDA_P$30") (pintype "bidirectional"))
      (node (ref "U$3") (pin "P$30") (pinfunction "SDA_P$30") (pintype "bidirectional"))
      (node (ref "U10") (pin "15") (pinfunction "SDA_15") (pintype "bidirectional"))
    )
    (net (code "72") (name "SW1_EN") (class "Default")
      (node (ref "U10") (pin "4") (pinfunction "IO0_4") (pintype "bidirectional"))
      (node (ref "U11") (pin "4") (pinfunction "EN_4") (pintype "input"))
    )
    (net (code "73") (name "SW2_EN") (class "Default")
      (node (ref "U10") (pin "5") (pinfunction "IO1_5") (pintype "bidirectional"))
      (node (ref "U12") (pin "4") (pinfunction "EN_4") (pintype "input"))
    )
    (net (code "74") (name "SW3_EN") (class "Default")
      (node (ref "U10") (pin "6") (pinfunction "IO2_6") (pintype "bidirectional"))
      (node (ref "U13") (pin "4") (pinfunction "EN_4") (pintype "input"))
    )
    (net (code "75") (name "UNPROTECTED3V3") (class "Default")
      (node (ref "C10") (pin "2") (pinfunction "2_2") (pintype "passive"))
      (node (ref "R21") (pin "1") (pinfunction "1_1") (pintype "passive"))
      (node (ref "R23") (pin "1") (pinfunction "1_1") (pintype "passive"))
      (node (ref "R6") (pin "1") (pinfunction "1_1") (pintype "passive"))
      (node (ref "R8") (pin "1") (pinfunction "1_1") (pintype "passive"))
      (node (ref "U11") (pin "6") (pinfunction "IN_6") (pintype "power_in"))
      (node (ref "U12") (pin "6") (pinfunction "IN_6") (pintype "power_in"))
      (node (ref "U13") (pin "6") (pinfunction "IN_6") (pintype "power_in"))
      (node (ref "U6") (pin "1") (pinfunction "VOUT_1") (pintype "output"))
      (node (ref "U6") (pin "10") (pinfunction "FB_10") (pintype "input"))
      (node (ref "U8") (pin "4") (pinfunction "EN_4") (pintype "input"))
      (node (ref "U8") (pin "6") (pinfunction "IN_6") (pintype "power_in"))
    )
    (net (code "76") (name "unconnected-(U1-PGOOD-Pad8)") (class "Default")
      (node (ref "U1") (pin "8") (pinfunction "PGOOD_8") (pintype "output"))
    )
    (net (code "77") (name "unconnected-(U2-PGOOD-Pad8)") (class "Default")
      (node (ref "U2") (pin "8") (pinfunction "PGOOD_8") (pintype "output"))
    )
    (net (code "78") (name "unconnected-(U3-PGOOD-Pad8)") (class "Default")
      (node (ref "U3") (pin "8") (pinfunction "PGOOD_8") (pintype "output"))
    )
    (net (code "79") (name "unconnected-(U4-NC-Pad7)") (class "Default")
      (node (ref "U4") (pin "7") (pinfunction "NC_7") (pintype "no_connect"))
    )
    (net (code "80") (name "unconnected-(U4-NC_2-Pad8)") (class "Default")
      (node (ref "U4") (pin "8") (pinfunction "NC_2_8") (pintype "no_connect"))
    )
    (net (code "81") (name "unconnected-(U5-NC-Pad7)") (class "Default")
      (node (ref "U5") (pin "7") (pinfunction "NC_7") (pintype "no_connect"))
    )
    (net (code "82") (name "unconnected-(U5-NC_2-Pad8)") (class "Default")
      (node (ref "U5") (pin "8") (pinfunction "NC_2_8") (pintype "no_connect"))
    )
    (net (code "83") (name "unconnected-(U9-VDPM-Pad9)") (class "Default")
      (node (ref "U9") (pin "9") (pinfunction "VDPM_9") (pintype "input"))
    )
    (net (code "84") (name "unconnected-(U9-~{CHG}-Pad8)") (class "Default")
      (node (ref "U9") (pin "8") (pinfunction "~{CHG}_8") (pintype "output"))
    )
    (net (code "85") (name "unconnected-(U10-A0-Pad1)") (class "Default")
      (node (ref "U10") (pin "1") (pinfunction "A0_1") (pintype "input"))
    )
    (net (code "86") (name "unconnected-(U10-A1-Pad2)") (class "Default")
      (node (ref "U10") (pin "2") (pinfunction "A1_2") (pintype "input"))
    )
    (net (code "87") (name "unconnected-(U10-A2-Pad3)") (class "Default")
      (node (ref "U10") (pin "3") (pinfunction "A2_3") (pintype "input"))
    )
    (net (code "88") (name "unconnected-(U10-IO3-Pad7)") (class "Default")
      (node (ref "U10") (pin "7") (pinfunction "IO3_7") (pintype "bidirectional"))
    )
    (net (code "89") (name "unconnected-(U10-IO4-Pad9)") (class "Default")
      (node (ref "U10") (pin "9") (pinfunction "IO4_9") (pintype "bidirectional"))
    )
    (net (code "90") (name "unconnected-(U10-IO5-Pad10)") (class "Default")
      (node (ref "U10") (pin "10") (pinfunction "IO5_10") (pintype "bidirectional"))
    )
    (net (code "91") (name "unconnected-(U10-IO6-Pad11)") (class "Default")
      (node (ref "U10") (pin "11") (pinfunction "IO6_11") (pintype "bidirectional"))
    )
    (net (code "92") (name "unconnected-(U10-IO7-Pad12)") (class "Default")
      (node (ref "U10") (pin "12") (pinfunction "IO7_12") (pintype "bidirectional"))
    )
    (net (code "93") (name "unconnected-(U10-~{INT}-Pad13)") (class "Default")
      (node (ref "U10") (pin "13") (pinfunction "~{INT}_13") (pintype "output"))
    )
  )
)
